# Copy_of_ST_LINK_V2-1.net
KiCad netlist of a schematic drawn in Altium Designer
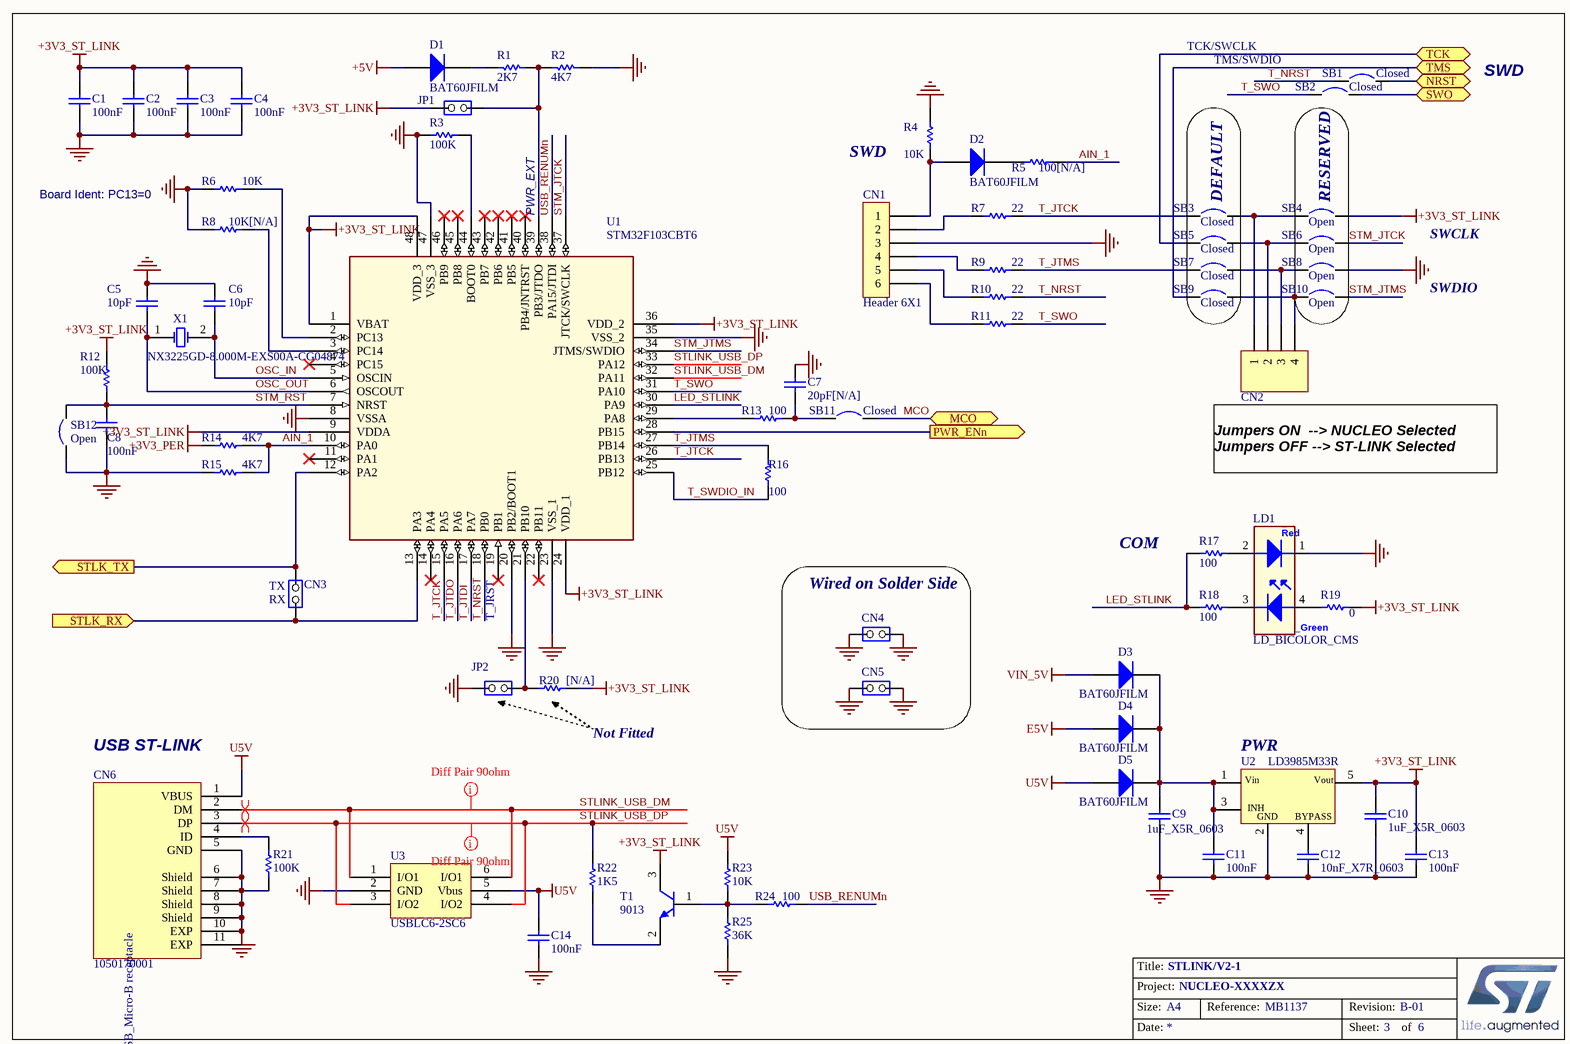
[diagram p0: Copy of ST_LINK_V2-1.SCHDOC]

(export (version "E")
  (design (tool "Eeschema 10.0.6"))
  (components
    (comp (ref "C1")
      (value "100nF")
      (footprint "0603C")
      (description "Capacitor 0402 / 0603 / 0805")
      (libsource (lib "MCD_TOOLS") (part "Capacitor_ST"))
    )
    (comp (ref "C2")
      (value "100nF")
      (footprint "0603C")
      (description "Capacitor 0402 / 0603 / 0805")
      (libsource (lib "MCD_TOOLS") (part "Capacitor_ST"))
    )
    (comp (ref "C3")
      (value "100nF")
      (footprint "0603C")
      (description "Capacitor 0402 / 0603 / 0805")
      (libsource (lib "MCD_TOOLS") (part "Capacitor_ST"))
    )
    (comp (ref "C4")
      (value "100nF")
      (footprint "0603C")
      (description "Capacitor 0402 / 0603 / 0805")
      (libsource (lib "MCD_TOOLS") (part "Capacitor_ST"))
    )
    (comp (ref "C5")
      (value "10pF")
      (footprint "0603C")
      (description "Capacitor 0402 / 0603 / 0805")
      (libsource (lib "MCD_TOOLS") (part "Capacitor_ST"))
    )
    (comp (ref "C6")
      (value "10pF")
      (footprint "0603C")
      (description "Capacitor 0402 / 0603 / 0805")
      (libsource (lib "MCD_TOOLS") (part "Capacitor_ST"))
    )
    (comp (ref "C7")
      (value "20pF[N/A]")
      (footprint "0603C")
      (description "Capacitor 0402 / 0603 / 0805")
      (libsource (lib "MCD_TOOLS") (part "Capacitor_ST"))
    )
    (comp (ref "C8")
      (value "100nF")
      (footprint "0603C")
      (description "Capacitor 0402 / 0603 / 0805")
      (libsource (lib "MCD_TOOLS") (part "Capacitor_ST"))
    )
    (comp (ref "C9")
      (value "1uF_X5R_0603")
      (footprint "0603C")
      (description "0603  X5R 1µF")
      (fields (field (name "TOLERANCE") "10%"))
      (libsource (lib "MB963_1") (part "CAP SMD 0603  X5R 1µF 25V 10%"))
    )
    (comp (ref "C10")
      (value "1uF_X5R_0603")
      (footprint "0603C")
      (description "0603  X5R 1µF")
      (fields (field (name "TOLERANCE") "10%"))
      (libsource (lib "MB963_1") (part "CAP SMD 0603  X5R 1µF 25V 10%"))
    )
    (comp (ref "C11")
      (value "100nF")
      (footprint "0603C")
      (description "Capacitor 0402 / 0603 / 0805")
      (libsource (lib "MCD_TOOLS") (part "Capacitor_ST"))
    )
    (comp (ref "C12")
      (value "10nF_X7R_0603")
      (footprint "0603C")
      (description "0603  X7R 10NF")
      (fields (field (name "TOLERANCE") "10%"))
      (libsource (lib "MB963_1") (part "CAP SMD 0603  X7R 10000PF 50V 10%"))
    )
    (comp (ref "C13")
      (value "100nF")
      (footprint "0603C")
      (description "Capacitor 0402 / 0603 / 0805")
      (libsource (lib "MCD_TOOLS") (part "Capacitor_ST"))
    )
    (comp (ref "C14")
      (value "100nF")
      (footprint "0603C")
      (description "Capacitor 0402 / 0603 / 0805")
      (libsource (lib "MCD_TOOLS") (part "Capacitor_ST"))
    )
    (comp (ref "CN1")
      (value "Header 6X1")
      (footprint "HDR_1x6_2R54_V_M")
      (description "Header, 6-Pin, Single row")
      (fields (field (name "PUBLISHER") "Altium Limited"))
      (libsource (lib "Nucleo_64") (part "Header 6X1"))
    )
    (comp (ref "CN2")
      (value "Header 4")
      (footprint "HDR_1x4_2R54_V_M")
      (description "Header, 4-Pin, Single row")
      (fields (field (name "PUBLISHER") "Altium Limited"))
      (libsource (lib "Nucleo_64") (part "Header 4"))
    )
    (comp (ref "CN3") (value "~") (footprint "HDR_1x2_2R54_V_M_S") (libsource (lib "MCD_TOOLS") (part "JP2")))
    (comp (ref "CN4") (value "~") (footprint "HDR_1x2_2R54_V_M") (libsource (lib "*") (part "JP2")))
    (comp (ref "CN5") (value "~") (footprint "HDR_1x2_2R54_V_M") (libsource (lib "*") (part "JP2")))
    (comp (ref "CN6")
      (value "1050170001")
      (footprint "Molex_1050170001")
      (libsource (lib "Smartphone_accessory") (part "1050170001"))
    )
    (comp (ref "D1")
      (value "BAT60JFILM")
      (footprint "SOD-323")
      (description "Default Diode")
      (fields (field (name "PUBLISHER") "Altium Limited"))
      (libsource (lib "MB1144_1") (part "Diode"))
    )
    (comp (ref "D2")
      (value "BAT60JFILM")
      (footprint "SOD-323")
      (libsource (lib "MB1137") (part "BAT60JFILM"))
    )
    (comp (ref "D3")
      (value "BAT60JFILM")
      (footprint "SOD-323")
      (libsource (lib "MB1137") (part "BAT60JFILM"))
    )
    (comp (ref "D4")
      (value "BAT60JFILM")
      (footprint "SOD-323")
      (libsource (lib "MB1137") (part "BAT60JFILM"))
    )
    (comp (ref "D5")
      (value "BAT60JFILM")
      (footprint "SOD-323")
      (libsource (lib "MB1137") (part "BAT60JFILM"))
    )
    (comp (ref "JP1") (value "~") (footprint "HDR_1x2_2R54_V_M_S") (libsource (lib "*") (part "JP2")))
    (comp (ref "JP2") (value "~") (footprint "HDR_1x2_2R54_V_M_S") (libsource (lib "*") (part "JP2")))
    (comp (ref "LD1")
      (value "LD_BICOLOR_CMS")
      (footprint "HSMF-A201")
      (description "Bicolor Led")
      (libsource (lib "MB1137") (part "LD_BICOLOR_CMS"))
    )
    (comp (ref "R1")
      (value "2K7")
      (footprint "0603R")
      (description "Resistor")
      (fields (field (name "PUBLISHER") "Altium Limited"))
      (libsource (lib "") (part "Res1_2"))
    )
    (comp (ref "R2")
      (value "4K7")
      (footprint "0603R")
      (description "Resistor")
      (fields (field (name "PUBLISHER") "Altium Limited"))
      (libsource (lib "") (part "Res1_2"))
    )
    (comp (ref "R3")
      (value "100K")
      (footprint "0603R")
      (description "Resistor 0402 / 0603 / 0805")
      (libsource (lib "Miscellaneous Devices") (part "Res1"))
    )
    (comp (ref "R4")
      (value "10K")
      (footprint "0603R")
      (description "Resistor 0402 / 0603 / 0805")
      (libsource (lib "Miscellaneous Devices") (part "Res1"))
    )
    (comp (ref "R5")
      (value "100[N/A]")
      (footprint "0603R")
      (description "Resistor 0402 / 0603 / 0805")
      (libsource (lib "Miscellaneous Devices") (part "Res1"))
    )
    (comp (ref "R6")
      (value "10K")
      (footprint "0603R")
      (description "Resistor 0402 / 0603 / 0805")
      (libsource (lib "Miscellaneous Devices") (part "Res1"))
    )
    (comp (ref "R7")
      (value "22")
      (footprint "0603R")
      (description "Resistor 0402 / 0603 / 0805")
      (libsource (lib "Miscellaneous Devices") (part "Res1"))
    )
    (comp (ref "R8")
      (value "10K[N/A]")
      (footprint "0603R")
      (description "Resistor 0402 / 0603 / 0805")
      (libsource (lib "Miscellaneous Devices") (part "Res1"))
    )
    (comp (ref "R9")
      (value "22")
      (footprint "0603R")
      (description "Resistor 0402 / 0603 / 0805")
      (libsource (lib "Miscellaneous Devices") (part "Res1"))
    )
    (comp (ref "R10")
      (value "22")
      (footprint "0603R")
      (description "Resistor 0402 / 0603 / 0805")
      (libsource (lib "Miscellaneous Devices") (part "Res1"))
    )
    (comp (ref "R11")
      (value "22")
      (footprint "0603R")
      (description "Resistor 0402 / 0603 / 0805")
      (libsource (lib "Miscellaneous Devices") (part "Res1"))
    )
    (comp (ref "R12")
      (value "100K")
      (footprint "0603R")
      (description "Resistor 0402 / 0603 / 0805")
      (libsource (lib "Miscellaneous Devices") (part "Res1"))
    )
    (comp (ref "R13")
      (value "100")
      (footprint "0603R")
      (description "Resistor 0402 / 0603 / 0805")
      (libsource (lib "Miscellaneous Devices") (part "Res1"))
    )
    (comp (ref "R14")
      (value "4K7")
      (footprint "0603R")
      (description "Resistor 0402 / 0603 / 0805")
      (libsource (lib "Miscellaneous Devices") (part "Res1"))
    )
    (comp (ref "R15")
      (value "4K7")
      (footprint "0603R")
      (description "Resistor 0402 / 0603 / 0805")
      (libsource (lib "Miscellaneous Devices") (part "Res1"))
    )
    (comp (ref "R16")
      (value "100")
      (footprint "0603R")
      (description "Resistor 0402 / 0603 / 0805")
      (libsource (lib "Miscellaneous Devices") (part "Res1"))
    )
    (comp (ref "R17")
      (value "100")
      (footprint "0603R")
      (description "Resistor 0402 / 0603 / 0805")
      (libsource (lib "Miscellaneous Devices") (part "Res1"))
    )
    (comp (ref "R18")
      (value "100")
      (footprint "0603R")
      (description "Resistor 0402 / 0603 / 0805")
      (libsource (lib "Miscellaneous Devices") (part "Res1"))
    )
    (comp (ref "R19")
      (value "0")
      (footprint "0603R")
      (description "Resistor 0402 / 0603 / 0805")
      (libsource (lib "Miscellaneous Devices") (part "Res1"))
    )
    (comp (ref "R20")
      (value "[N/A]")
      (footprint "0603R")
      (description "Resistor")
      (fields (field (name "PUBLISHER") "Altium Limited"))
      (libsource (lib "") (part "Res1_1"))
    )
    (comp (ref "R21")
      (value "100K")
      (footprint "0603R")
      (description "Resistor 0402 / 0603 / 0805")
      (libsource (lib "Miscellaneous Devices") (part "Res1"))
    )
    (comp (ref "R22")
      (value "1K5")
      (footprint "0603R")
      (description "Resistor 0402 / 0603 / 0805")
      (libsource (lib "Miscellaneous Devices") (part "Res1"))
    )
    (comp (ref "R23")
      (value "10K")
      (footprint "0603R")
      (description "Resistor")
      (fields (field (name "PUBLISHER") "Altium Limited"))
      (libsource (lib "") (part "Res1_1"))
    )
    (comp (ref "R24")
      (value "100")
      (footprint "0603R")
      (description "Resistor 0402 / 0603 / 0805")
      (libsource (lib "Miscellaneous Devices") (part "Res1"))
    )
    (comp (ref "R25")
      (value "36K")
      (footprint "0603R")
      (description "Resistor")
      (fields (field (name "PUBLISHER") "Altium Limited"))
      (libsource (lib "") (part "Res1_1"))
    )
    (comp (ref "SB1")
      (value "Closed")
      (footprint "SB_0603")
      (description "Circuit Breaker")
      (fields (field (name "PUBLISHER") "Altium Limited"))
      (libsource (lib "MB1167") (part "Circuit Breaker_close"))
    )
    (comp (ref "SB2")
      (value "Closed")
      (footprint "SB_0603")
      (description "Circuit Breaker")
      (fields (field (name "PUBLISHER") "Altium Limited"))
      (libsource (lib "MB1167") (part "Circuit Breaker_close"))
    )
    (comp (ref "SB3")
      (value "Closed")
      (footprint "SB_0603")
      (description "Circuit Breaker")
      (fields (field (name "PUBLISHER") "Altium Limited"))
      (libsource (lib "MB1167") (part "Circuit Breaker_close"))
    )
    (comp (ref "SB4")
      (value "Open")
      (footprint "SB_0603")
      (description "Circuit Breaker")
      (fields (field (name "PUBLISHER") "Altium Limited"))
      (libsource (lib "MB1167") (part "Circuit Breaker"))
    )
    (comp (ref "SB5")
      (value "Closed")
      (footprint "SB_0603")
      (description "Circuit Breaker")
      (fields (field (name "PUBLISHER") "Altium Limited"))
      (libsource (lib "MB1167") (part "Circuit Breaker_close"))
    )
    (comp (ref "SB6")
      (value "Open")
      (footprint "SB_0603")
      (description "Circuit Breaker")
      (fields (field (name "PUBLISHER") "Altium Limited"))
      (libsource (lib "MB1167") (part "Circuit Breaker"))
    )
    (comp (ref "SB7")
      (value "Closed")
      (footprint "SB_0603")
      (description "Circuit Breaker")
      (fields (field (name "PUBLISHER") "Altium Limited"))
      (libsource (lib "MB1167") (part "Circuit Breaker_close"))
    )
    (comp (ref "SB8")
      (value "Open")
      (footprint "SB_0603")
      (description "Circuit Breaker")
      (fields (field (name "PUBLISHER") "Altium Limited"))
      (libsource (lib "MB1167") (part "Circuit Breaker"))
    )
    (comp (ref "SB9")
      (value "Closed")
      (footprint "SB_0603")
      (description "Circuit Breaker")
      (fields (field (name "PUBLISHER") "Altium Limited"))
      (libsource (lib "MB1167") (part "Circuit Breaker_close"))
    )
    (comp (ref "SB10")
      (value "Open")
      (footprint "SB_0603")
      (description "Circuit Breaker")
      (fields (field (name "PUBLISHER") "Altium Limited"))
      (libsource (lib "MB1167") (part "Circuit Breaker"))
    )
    (comp (ref "SB11")
      (value "Closed")
      (footprint "SB_0603")
      (description "Circuit Breaker")
      (fields (field (name "PUBLISHER") "Altium Limited"))
      (libsource (lib "MB1167") (part "Circuit Breaker_close"))
    )
    (comp (ref "SB12")
      (value "Open")
      (footprint "SB_0603")
      (description "Circuit Breaker")
      (fields (field (name "PUBLISHER") "Altium Limited"))
      (libsource (lib "MB1167") (part "Circuit Breaker"))
    )
    (comp (ref "T1")
      (value "9013")
      (footprint "SOT-23")
      (description "NPN Bipolar Transistor")
      (fields (field (name "PUBLISHER") "Altium Limited"))
      (libsource (lib "MB1167") (part "NPN"))
    )
    (comp (ref "U1")
      (value "STM32F103CBT6")
      (footprint "LQFP48_0R5_7x7")
      (description "Medium-density performance line ARM-based 32-bit MCU with 64KB Flash")
      (libsource (lib "Nucleo_64") (part "STM32F103CBT6"))
    )
    (comp (ref "U2")
      (value "LD3985M33R")
      (footprint "SOT-23-5L")
      (description "Ultra low drop-low noise BiCMOS voltage, regulators low ESR capacitors compatible")
      (libsource (lib "MCD_TOOLS") (part "LD3985M33R"))
    )
    (comp (ref "U3")
      (value "USBLC6-2SC6")
      (footprint "SOT23-6L")
      (libsource (lib "MB1137") (part "USBLC6-2SC6"))
    )
    (comp (ref "X1")
      (value "NX3225GD-8.000M-EXS00A-CG04874")
      (footprint "OSC_2SM_3R2x2R5")
      (description "Crystal Oscillator")
      (fields (field (name "PUBLISHER") "Altium Limited"))
      (libsource (lib "MB963_1") (part "XTAL"))
    )
  )
  (nets
    (net (code "1") (name "+3V3_PER") (class "Default")
      (node (ref "R14") (pin "1") (pinfunction "1_1") (pintype "passive"))
    )
    (net (code "2") (name "+3V3_ST_LINK") (class "Default")
      (node (ref "C1") (pin "2") (pinfunction "2_2") (pintype "passive"))
      (node (ref "C10") (pin "1") (pinfunction "1_1") (pintype "passive"))
      (node (ref "C13") (pin "2") (pinfunction "2_2") (pintype "passive"))
      (node (ref "C2") (pin "2") (pinfunction "2_2") (pintype "passive"))
      (node (ref "C3") (pin "2") (pinfunction "2_2") (pintype "passive"))
      (node (ref "C4") (pin "2") (pinfunction "2_2") (pintype "passive"))
      (node (ref "JP1") (pin "1") (pinfunction "COMMON_1") (pintype "passive"))
      (node (ref "R12") (pin "2") (pinfunction "2_2") (pintype "passive"))
      (node (ref "R19") (pin "2") (pinfunction "2_2") (pintype "passive"))
      (node (ref "R20") (pin "1") (pinfunction "1_1") (pintype "passive"))
      (node (ref "SB4") (pin "2") (pinfunction "2_2") (pintype "passive"))
      (node (ref "T1") (pin "3") (pinfunction "C_3") (pintype "passive"))
      (node (ref "U1") (pin "1") (pinfunction "VBAT_1") (pintype "power_in"))
      (node (ref "U1") (pin "24") (pinfunction "VDD_1_24") (pintype "power_in"))
      (node (ref "U1") (pin "36") (pinfunction "VDD_2_36") (pintype "power_in"))
      (node (ref "U1") (pin "48") (pinfunction "VDD_3_48") (pintype "power_in"))
      (node (ref "U1") (pin "9") (pinfunction "VDDA_9") (pintype "power_in"))
      (node (ref "U2") (pin "5") (pinfunction "Vout_5") (pintype "passive"))
    )
    (net (code "3") (name "+5V") (class "Default")
      (node (ref "D1") (pin "1") (pinfunction "A_1") (pintype "passive"))
    )
    (net (code "4") (name "/AIN_1") (class "Default")
      (node (ref "R14") (pin "2") (pinfunction "2_2") (pintype "passive"))
      (node (ref "R15") (pin "2") (pinfunction "2_2") (pintype "passive"))
      (node (ref "R5") (pin "2") (pinfunction "2_2") (pintype "passive"))
      (node (ref "U1") (pin "10") (pinfunction "PA0_10") (pintype "bidirectional"))
    )
    (net (code "5") (name "/LED_STLINK") (class "Default")
      (node (ref "R17") (pin "1") (pinfunction "1_1") (pintype "passive"))
      (node (ref "R18") (pin "1") (pinfunction "1_1") (pintype "passive"))
      (node (ref "U1") (pin "30") (pinfunction "PA9_30") (pintype "bidirectional"))
    )
    (net (code "6") (name "/MCO") (class "Default")
      (node (ref "SB11") (pin "2") (pinfunction "2_2") (pintype "passive"))
    )
    (net (code "7") (name "/NRST") (class "Default")
      (node (ref "SB1") (pin "2") (pinfunction "2_2") (pintype "passive"))
    )
    (net (code "8") (name "/OSC_IN") (class "Default")
      (node (ref "C6") (pin "1") (pinfunction "1_1") (pintype "passive"))
      (node (ref "U1") (pin "5") (pinfunction "OSCIN_5") (pintype "input"))
      (node (ref "X1") (pin "2") (pinfunction "OSC2_2") (pintype "passive"))
    )
    (net (code "9") (name "/OSC_OUT") (class "Default")
      (node (ref "C5") (pin "1") (pinfunction "1_1") (pintype "passive"))
      (node (ref "U1") (pin "6") (pinfunction "OSCOUT_6") (pintype "output"))
      (node (ref "X1") (pin "1") (pinfunction "OSC1_1") (pintype "passive"))
    )
    (net (code "10") (name "/PWR_ENn") (class "Default")
      (node (ref "U1") (pin "28") (pinfunction "PB15_28") (pintype "bidirectional"))
    )
    (net (code "11") (name "/STLINK_USB_DM") (class "Default")
      (node (ref "CN6") (pin "2") (pinfunction "DM_2") (pintype "passive"))
      (node (ref "U1") (pin "32") (pinfunction "PA11_32") (pintype "bidirectional"))
      (node (ref "U3") (pin "1") (pinfunction "I/O1_1") (pintype "passive"))
      (node (ref "U3") (pin "6") (pinfunction "I/O1_6") (pintype "passive"))
    )
    (net (code "12") (name "/STLINK_USB_DP") (class "Default")
      (node (ref "CN6") (pin "3") (pinfunction "DP_3") (pintype "passive"))
      (node (ref "R22") (pin "1") (pinfunction "1_1") (pintype "passive"))
      (node (ref "U1") (pin "33") (pinfunction "PA12_33") (pintype "bidirectional"))
      (node (ref "U3") (pin "3") (pinfunction "I/O2_3") (pintype "passive"))
      (node (ref "U3") (pin "4") (pinfunction "I/O2_4") (pintype "passive"))
    )
    (net (code "13") (name "/STLK_RX") (class "Default")
      (node (ref "CN3") (pin "1") (pinfunction "COMMON_1") (pintype "passive"))
      (node (ref "U1") (pin "13") (pinfunction "PA3_13") (pintype "bidirectional"))
    )
    (net (code "14") (name "/STLK_TX") (class "Default")
      (node (ref "CN3") (pin "2") (pinfunction "NO_2") (pintype "passive"))
      (node (ref "U1") (pin "12") (pinfunction "PA2_12") (pintype "bidirectional"))
    )
    (net (code "15") (name "/STM_JTCK") (class "Default")
      (node (ref "SB6") (pin "2") (pinfunction "2_2") (pintype "passive"))
      (node (ref "U1") (pin "37") (pinfunction "JTCK/SWCLK_37") (pintype "bidirectional"))
    )
    (net (code "16") (name "/STM_JTMS") (class "Default")
      (node (ref "SB10") (pin "2") (pinfunction "2_2") (pintype "passive"))
      (node (ref "U1") (pin "34") (pinfunction "JTMS/SWDIO_34") (pintype "bidirectional"))
    )
    (net (code "17") (name "/STM_RST") (class "Default")
      (node (ref "C8") (pin "2") (pinfunction "2_2") (pintype "passive"))
      (node (ref "R12") (pin "1") (pinfunction "1_1") (pintype "passive"))
      (node (ref "SB12") (pin "2") (pinfunction "2_2") (pintype "passive"))
      (node (ref "U1") (pin "7") (pinfunction "NRST_7") (pintype "input"))
    )
    (net (code "18") (name "/SWO") (class "Default")
      (node (ref "SB2") (pin "2") (pinfunction "2_2") (pintype "passive"))
    )
    (net (code "19") (name "/TCK") (class "Default")
      (node (ref "SB5") (pin "1") (pinfunction "1_1") (pintype "passive"))
    )
    (net (code "20") (name "/TMS") (class "Default")
      (node (ref "SB9") (pin "1") (pinfunction "1_1") (pintype "passive"))
    )
    (net (code "21") (name "/T_JTCK") (class "Default")
      (node (ref "R7") (pin "2") (pinfunction "2_2") (pintype "passive"))
      (node (ref "SB3") (pin "1") (pinfunction "1_1") (pintype "passive"))
      (node (ref "U1") (pin "15") (pinfunction "PA5_15") (pintype "bidirectional"))
      (node (ref "U1") (pin "26") (pinfunction "PB13_26") (pintype "bidirectional"))
    )
    (net (code "22") (name "/T_JTDI") (class "Default")
      (node (ref "U1") (pin "17") (pinfunction "PA7_17") (pintype "bidirectional"))
    )
    (net (code "23") (name "/T_JTDO") (class "Default")
      (node (ref "U1") (pin "16") (pinfunction "PA6_16") (pintype "bidirectional"))
    )
    (net (code "24") (name "/T_JTMS") (class "Default")
      (node (ref "R16") (pin "2") (pinfunction "2_2") (pintype "passive"))
      (node (ref "R9") (pin "2") (pinfunction "2_2") (pintype "passive"))
      (node (ref "SB7") (pin "1") (pinfunction "1_1") (pintype "passive"))
      (node (ref "U1") (pin "27") (pinfunction "PB14_27") (pintype "bidirectional"))
    )
    (net (code "25") (name "/T_NRST") (class "Default")
      (node (ref "R10") (pin "2") (pinfunction "2_2") (pintype "passive"))
      (node (ref "SB1") (pin "1") (pinfunction "1_1") (pintype "passive"))
      (node (ref "U1") (pin "18") (pinfunction "PB0_18") (pintype "bidirectional"))
    )
    (net (code "26") (name "/T_SWDIO_IN") (class "Default")
      (node (ref "R16") (pin "1") (pinfunction "1_1") (pintype "passive"))
      (node (ref "U1") (pin "25") (pinfunction "PB12_25") (pintype "bidirectional"))
    )
    (net (code "27") (name "/T_SWO") (class "Default")
      (node (ref "R11") (pin "2") (pinfunction "2_2") (pintype "passive"))
      (node (ref "SB2") (pin "1") (pinfunction "1_1") (pintype "passive"))
      (node (ref "U1") (pin "31") (pinfunction "PA10_31") (pintype "bidirectional"))
    )
    (net (code "28") (name "/USB_RENUMn") (class "Default")
      (node (ref "R24") (pin "2") (pinfunction "2_2") (pintype "passive"))
      (node (ref "U1") (pin "38") (pinfunction "PA15/JTDI_38") (pintype "bidirectional"))
    )
    (net (code "29") (name "E5V") (class "Default")
      (node (ref "D4") (pin "1") (pinfunction "A_1") (pintype "passive"))
    )
    (net (code "30") (name "GND") (class "Default")
      (node (ref "C1") (pin "1") (pinfunction "1_1") (pintype "passive"))
      (node (ref "C10") (pin "2") (pinfunction "2_2") (pintype "passive"))
      (node (ref "C11") (pin "1") (pinfunction "1_1") (pintype "passive"))
      (node (ref "C12") (pin "1") (pinfunction "1_1") (pintype "passive"))
      (node (ref "C13") (pin "1") (pinfunction "1_1") (pintype "passive"))
      (node (ref "C14") (pin "1") (pinfunction "1_1") (pintype "passive"))
      (node (ref "C2") (pin "1") (pinfunction "1_1") (pintype "passive"))
      (node (ref "C3") (pin "1") (pinfunction "1_1") (pintype "passive"))
      (node (ref "C4") (pin "1") (pinfunction "1_1") (pintype "passive"))
      (node (ref "C5") (pin "2") (pinfunction "2_2") (pintype "passive"))
      (node (ref "C6") (pin "2") (pinfunction "2_2") (pintype "passive"))
      (node (ref "C7") (pin "2") (pinfunction "2_2") (pintype "passive"))
      (node (ref "C8") (pin "1") (pinfunction "1_1") (pintype "passive"))
      (node (ref "C9") (pin "1") (pinfunction "1_1") (pintype "passive"))
      (node (ref "CN1") (pin "3") (pinfunction "3_3") (pintype "passive"))
      (node (ref "CN4") (pin "1") (pinfunction "COMMON_1") (pintype "passive"))
      (node (ref "CN4") (pin "2") (pinfunction "NO_2") (pintype "passive"))
      (node (ref "CN5") (pin "1") (pinfunction "COMMON_1") (pintype "passive"))
      (node (ref "CN5") (pin "2") (pinfunction "NO_2") (pintype "passive"))
      (node (ref "CN6") (pin "10") (pinfunction "EXP_10") (pintype "passive"))
      (node (ref "CN6") (pin "5") (pinfunction "GND_5") (pintype "passive"))
      (node (ref "CN6") (pin "6") (pinfunction "Shield_6") (pintype "passive"))
      (node (ref "CN6") (pin "7") (pinfunction "Shield_7") (pintype "passive"))
      (node (ref "CN6") (pin "8") (pinfunction "Shield_8") (pintype "passive"))
      (node (ref "CN6") (pin "9") (pinfunction "Shield_9") (pintype "passive"))
      (node (ref "JP2") (pin "1") (pinfunction "COMMON_1") (pintype "passive"))
      (node (ref "LD1") (pin "1") (pinfunction "1_1") (pintype "passive"))
      (node (ref "R15") (pin "1") (pinfunction "1_1") (pintype "passive"))
      (node (ref "R2") (pin "2") (pinfunction "2_2") (pintype "passive"))
      (node (ref "R21") (pin "2") (pinfunction "2_2") (pintype "passive"))
      (node (ref "R25") (pin "1") (pinfunction "1_1") (pintype "passive"))
      (node (ref "R3") (pin "1") (pinfunction "1_1") (pintype "passive"))
      (node (ref "R4") (pin "2") (pinfunction "2_2") (pintype "passive"))
      (node (ref "R6") (pin "1") (pinfunction "1_1") (pintype "passive"))
      (node (ref "R8") (pin "1") (pinfunction "1_1") (pintype "passive"))
      (node (ref "SB12") (pin "1") (pinfunction "1_1") (pintype "passive"))
      (node (ref "SB8") (pin "2") (pinfunction "2_2") (pintype "passive"))
      (node (ref "U1") (pin "20") (pinfunction "PB2/BOOT1_20") (pintype "bidirectional"))
      (node (ref "U1") (pin "23") (pinfunction "VSS_1_23") (pintype "power_in"))
      (node (ref "U1") (pin "35") (pinfunction "VSS_2_35") (pintype "power_in"))
      (node (ref "U1") (pin "47") (pinfunction "VSS_3_47") (pintype "power_in"))
      (node (ref "U1") (pin "8") (pinfunction "VSSA_8") (pintype "power_in"))
      (node (ref "U2") (pin "2") (pinfunction "GND_2") (pintype "passive"))
      (node (ref "U3") (pin "2") (pinfunction "GND_2") (pintype "passive"))
    )
    (net (code "31") (name "Net-(C7-Pad1)") (class "Default")
      (node (ref "C7") (pin "1") (pinfunction "1_1") (pintype "passive"))
      (node (ref "R13") (pin "2") (pinfunction "2_2") (pintype "passive"))
      (node (ref "SB11") (pin "1") (pinfunction "1_1") (pintype "passive"))
    )
    (net (code "32") (name "Net-(CN1-Pad2)") (class "Default")
      (node (ref "CN1") (pin "2") (pinfunction "2_2") (pintype "passive"))
      (node (ref "R7") (pin "1") (pinfunction "1_1") (pintype "passive"))
    )
    (net (code "33") (name "Net-(CN1-Pad4)") (class "Default")
      (node (ref "CN1") (pin "4") (pinfunction "4_4") (pintype "passive"))
      (node (ref "R9") (pin "1") (pinfunction "1_1") (pintype "passive"))
    )
    (net (code "34") (name "Net-(CN1-Pad5)") (class "Default")
      (node (ref "CN1") (pin "5") (pinfunction "5_5") (pintype "passive"))
      (node (ref "R10") (pin "1") (pinfunction "1_1") (pintype "passive"))
    )
    (net (code "35") (name "Net-(CN1-Pad6)") (class "Default")
      (node (ref "CN1") (pin "6") (pinfunction "6_6") (pintype "passive"))
      (node (ref "R11") (pin "1") (pinfunction "1_1") (pintype "passive"))
    )
    (net (code "36") (name "Net-(CN2-Pad1)") (class "Default")
      (node (ref "CN2") (pin "1") (pinfunction "1_1") (pintype "passive"))
      (node (ref "SB3") (pin "2") (pinfunction "2_2") (pintype "passive"))
      (node (ref "SB4") (pin "1") (pinfunction "1_1") (pintype "passive"))
    )
    (net (code "37") (name "Net-(CN2-Pad2)") (class "Default")
      (node (ref "CN2") (pin "2") (pinfunction "2_2") (pintype "passive"))
      (node (ref "SB5") (pin "2") (pinfunction "2_2") (pintype "passive"))
      (node (ref "SB6") (pin "1") (pinfunction "1_1") (pintype "passive"))
    )
    (net (code "38") (name "Net-(CN2-Pad3)") (class "Default")
      (node (ref "CN2") (pin "3") (pinfunction "3_3") (pintype "passive"))
      (node (ref "SB7") (pin "2") (pinfunction "2_2") (pintype "passive"))
      (node (ref "SB8") (pin "1") (pinfunction "1_1") (pintype "passive"))
    )
    (net (code "39") (name "Net-(CN2-Pad4)") (class "Default")
      (node (ref "CN2") (pin "4") (pinfunction "4_4") (pintype "passive"))
      (node (ref "SB10") (pin "1") (pinfunction "1_1") (pintype "passive"))
      (node (ref "SB9") (pin "2") (pinfunction "2_2") (pintype "passive"))
    )
    (net (code "40") (name "Net-(CN6-ID)") (class "Default")
      (node (ref "CN6") (pin "4") (pinfunction "ID_4") (pintype "passive"))
      (node (ref "R21") (pin "1") (pinfunction "1_1") (pintype "passive"))
    )
    (net (code "41") (name "Net-(D1-K)") (class "Default")
      (node (ref "D1") (pin "2") (pinfunction "K_2") (pintype "passive"))
      (node (ref "R1") (pin "1") (pinfunction "1_1") (pintype "passive"))
    )
    (net (code "42") (name "Net-(D2-A)") (class "Default")
      (node (ref "CN1") (pin "1") (pinfunction "1_1") (pintype "passive"))
      (node (ref "D2") (pin "1") (pinfunction "A_1") (pintype "passive"))
      (node (ref "R4") (pin "1") (pinfunction "1_1") (pintype "passive"))
    )
    (net (code "43") (name "Net-(D2-K)") (class "Default")
      (node (ref "D2") (pin "2") (pinfunction "K_2") (pintype "passive"))
      (node (ref "R5") (pin "1") (pinfunction "1_1") (pintype "passive"))
    )
    (net (code "44") (name "Net-(D3-K)") (class "Default")
      (node (ref "C11") (pin "2") (pinfunction "2_2") (pintype "passive"))
      (node (ref "C9") (pin "2") (pinfunction "2_2") (pintype "passive"))
      (node (ref "D3") (pin "2") (pinfunction "K_2") (pintype "passive"))
      (node (ref "D4") (pin "2") (pinfunction "K_2") (pintype "passive"))
      (node (ref "D5") (pin "2") (pinfunction "K_2") (pintype "passive"))
      (node (ref "U2") (pin "1") (pinfunction "Vin_1") (pintype "passive"))
      (node (ref "U2") (pin "3") (pinfunction "CE_3") (pintype "passive"))
    )
    (net (code "45") (name "Net-(JP1-NO)") (class "Default")
      (node (ref "JP1") (pin "2") (pinfunction "NO_2") (pintype "passive"))
      (node (ref "R1") (pin "2") (pinfunction "2_2") (pintype "passive"))
      (node (ref "R2") (pin "1") (pinfunction "1_1") (pintype "passive"))
      (node (ref "U1") (pin "39") (pinfunction "PB3/JTDO_39") (pintype "bidirectional"))
    )
    (net (code "46") (name "Net-(JP2-NO)") (class "Default")
      (node (ref "JP2") (pin "2") (pinfunction "NO_2") (pintype "passive"))
      (node (ref "R20") (pin "2") (pinfunction "2_2") (pintype "passive"))
      (node (ref "U1") (pin "21") (pinfunction "PB10_21") (pintype "bidirectional"))
    )
    (net (code "47") (name "Net-(LD1-Pad2)") (class "Default")
      (node (ref "LD1") (pin "2") (pinfunction "2_2") (pintype "passive"))
      (node (ref "R17") (pin "2") (pinfunction "2_2") (pintype "passive"))
    )
    (net (code "48") (name "Net-(LD1-Pad3)") (class "Default")
      (node (ref "LD1") (pin "3") (pinfunction "3_3") (pintype "passive"))
      (node (ref "R18") (pin "2") (pinfunction "2_2") (pintype "passive"))
    )
    (net (code "49") (name "Net-(LD1-Pad4)") (class "Default")
      (node (ref "LD1") (pin "4") (pinfunction "4_4") (pintype "passive"))
      (node (ref "R19") (pin "1") (pinfunction "1_1") (pintype "passive"))
    )
    (net (code "50") (name "Net-(T1-B)") (class "Default")
      (node (ref "R23") (pin "1") (pinfunction "1_1") (pintype "passive"))
      (node (ref "R24") (pin "1") (pinfunction "1_1") (pintype "passive"))
      (node (ref "R25") (pin "2") (pinfunction "2_2") (pintype "passive"))
      (node (ref "T1") (pin "1") (pinfunction "B_1") (pintype "passive"))
    )
    (net (code "51") (name "Net-(T1-E)") (class "Default")
      (node (ref "R22") (pin "2") (pinfunction "2_2") (pintype "passive"))
      (node (ref "T1") (pin "2") (pinfunction "E_2") (pintype "passive"))
    )
    (net (code "52") (name "Net-(U1-BOOT0)") (class "Default")
      (node (ref "R3") (pin "2") (pinfunction "2_2") (pintype "passive"))
      (node (ref "U1") (pin "44") (pinfunction "BOOT0_44") (pintype "bidirectional"))
    )
    (net (code "53") (name "Net-(U1-PA8)") (class "Default")
      (node (ref "R13") (pin "1") (pinfunction "1_1") (pintype "passive"))
      (node (ref "U1") (pin "29") (pinfunction "PA8_29") (pintype "bidirectional"))
    )
    (net (code "54") (name "Net-(U1-PC13)") (class "Default")
      (node (ref "R6") (pin "2") (pinfunction "2_2") (pintype "passive"))
      (node (ref "U1") (pin "2") (pinfunction "PC13_2") (pintype "bidirectional"))
    )
    (net (code "55") (name "Net-(U1-PC14)") (class "Default")
      (node (ref "R8") (pin "2") (pinfunction "2_2") (pintype "passive"))
      (node (ref "U1") (pin "3") (pinfunction "PC14_3") (pintype "bidirectional"))
    )
    (net (code "56") (name "Net-(U2-BYPASS)") (class "Default")
      (node (ref "C12") (pin "2") (pinfunction "2_2") (pintype "passive"))
      (node (ref "U2") (pin "4") (pinfunction "BYPASS_4") (pintype "passive"))
    )
    (net (code "57") (name "U5V") (class "Default")
      (node (ref "C14") (pin "2") (pinfunction "2_2") (pintype "passive"))
      (node (ref "CN6") (pin "1") (pinfunction "VBUS_1") (pintype "passive"))
      (node (ref "D5") (pin "1") (pinfunction "A_1") (pintype "passive"))
      (node (ref "R23") (pin "2") (pinfunction "2_2") (pintype "passive"))
      (node (ref "U3") (pin "5") (pinfunction "Vbus_5") (pintype "passive"))
    )
    (net (code "58") (name "VIN_5V") (class "Default")
      (node (ref "D3") (pin "1") (pinfunction "A_1") (pintype "passive"))
    )
    (net (code "59") (name "unconnected-(CN6-EXP-Pad11)") (class "Default")
      (node (ref "CN6") (pin "11") (pinfunction "EXP_11") (pintype "passive"))
    )
    (net (code "60") (name "unconnected-(U1-PA1-Pad11)") (class "Default")
      (node (ref "U1") (pin "11") (pinfunction "PA1_11") (pintype "bidirectional+no_connect"))
    )
    (net (code "61") (name "unconnected-(U1-PA4-Pad14)") (class "Default")
      (node (ref "U1") (pin "14") (pinfunction "PA4_14") (pintype "bidirectional+no_connect"))
    )
    (net (code "62") (name "unconnected-(U1-PB1-Pad19)") (class "Default")
      (node (ref "U1") (pin "19") (pinfunction "PB1_19") (pintype "input+no_connect"))
    )
    (net (code "63") (name "unconnected-(U1-PB4{slash}JNTRST-Pad40)") (class "Default")
      (node (ref "U1") (pin "40") (pinfunction "PB4/JNTRST_40") (pintype "bidirectional+no_connect"))
    )
    (net (code "64") (name "unconnected-(U1-PB5-Pad41)") (class "Default")
      (node (ref "U1") (pin "41") (pinfunction "PB5_41") (pintype "bidirectional+no_connect"))
    )
    (net (code "65") (name "unconnected-(U1-PB6-Pad42)") (class "Default")
      (node (ref "U1") (pin "42") (pinfunction "PB6_42") (pintype "bidirectional+no_connect"))
    )
    (net (code "66") (name "unconnected-(U1-PB7-Pad43)") (class "Default")
      (node (ref "U1") (pin "43") (pinfunction "PB7_43") (pintype "bidirectional+no_connect"))
    )
    (net (code "67") (name "unconnected-(U1-PB8-Pad45)") (class "Default")
      (node (ref "U1") (pin "45") (pinfunction "PB8_45") (pintype "bidirectional+no_connect"))
    )
    (net (code "68") (name "unconnected-(U1-PB9-Pad46)") (class "Default")
      (node (ref "U1") (pin "46") (pinfunction "PB9_46") (pintype "bidirectional+no_connect"))
    )
    (net (code "69") (name "unconnected-(U1-PB11-Pad22)") (class "Default")
      (node (ref "U1") (pin "22") (pinfunction "PB11_22") (pintype "bidirectional+no_connect"))
    )
    (net (code "70") (name "unconnected-(U1-PC15-Pad4)") (class "Default")
      (node (ref "U1") (pin "4") (pinfunction "PC15_4") (pintype "bidirectional+no_connect"))
    )
  )
)
